# control.net
KiCad netlist of a schematic drawn in EAGLE
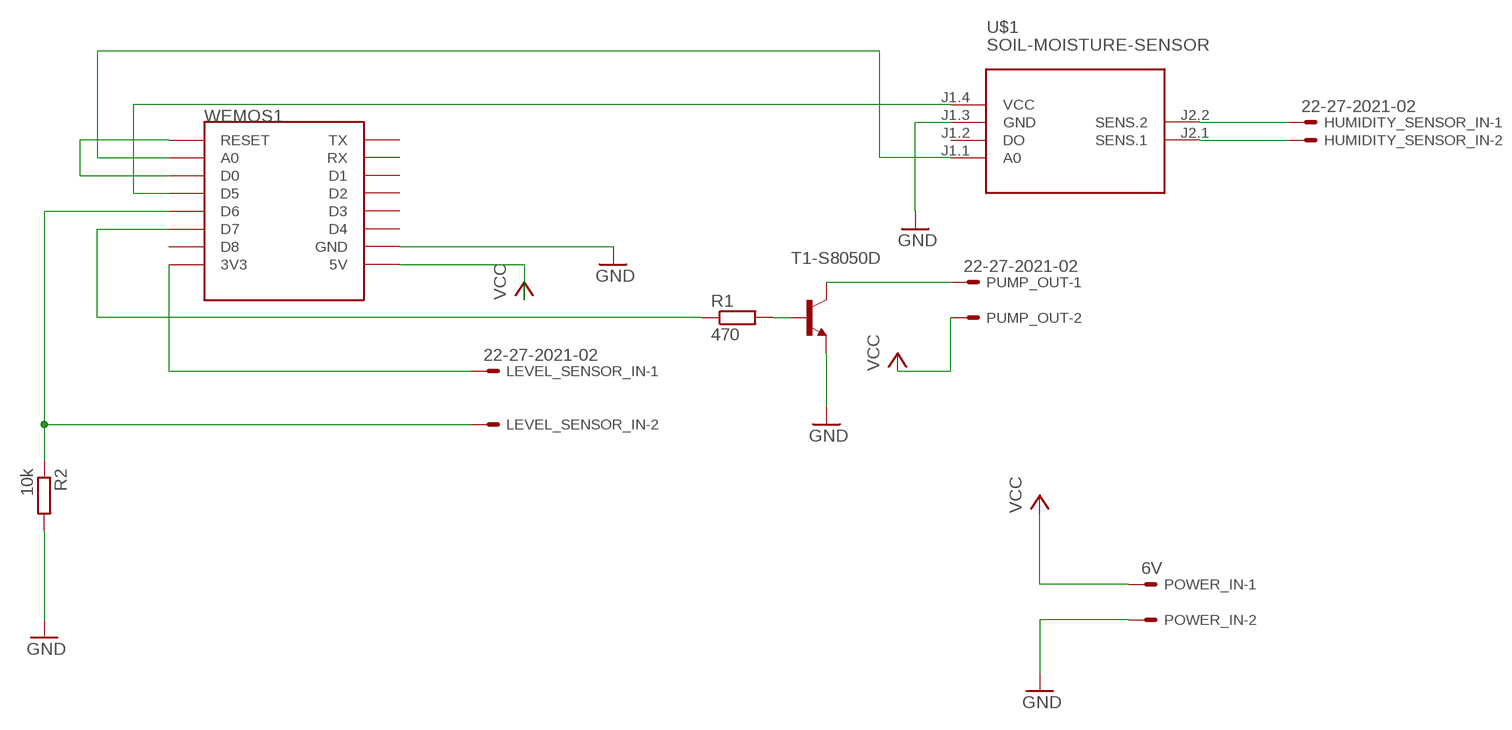
[diagram p0: schematic, sheet 1]

(export (version "E")
  (design (tool "Eeschema 10.0.6"))
  (components
    (comp (ref "HUMIDITY_SENSOR_IN")
      (value "22-27-2021-02")
      (footprint "eagle-import:6410-02")
      (fields (field (name "MF") "MOLEX"))
      (libsource (lib "eagle-import") (part "22-?-0227-2021"))
    )
    (comp (ref "LEVEL_SENSOR_IN")
      (value "22-27-2021-02")
      (footprint "eagle-import:6410-02")
      (fields (field (name "MF") "MOLEX"))
      (libsource (lib "eagle-import") (part "22-?-0227-2021"))
    )
    (comp (ref "POWER_IN")
      (value "6V")
      (footprint "eagle-import:6410-02")
      (fields (field (name "MF") "MOLEX"))
      (libsource (lib "eagle-import") (part "22-?-0227-2021"))
    )
    (comp (ref "PUMP_OUT")
      (value "22-27-2021-02")
      (footprint "eagle-import:6410-02")
      (fields (field (name "MF") "MOLEX"))
      (libsource (lib "eagle-import") (part "22-?-0227-2021"))
    )
    (comp (ref "R1")
      (value "470")
      (footprint "eagle-import:0204_7")
      (libsource (lib "eagle-import") (part "R0204/7"))
    )
    (comp (ref "R2")
      (value "10k")
      (footprint "eagle-import:0204_7")
      (libsource (lib "eagle-import") (part "R0204/7"))
    )
    (comp (ref "T1-S8050D")
      (value "-NPN-TO92")
      (footprint "eagle-import:TO92")
      (libsource (lib "eagle-import") (part "-NPN-TO92"))
    )
    (comp (ref "U$1")
      (value "SOIL-MOISTURE-SENSOR")
      (footprint "eagle-import:SOIL-MOISTURE-SENSOR")
      (libsource (lib "eagle-import") (part "SOIL-MOISTURE-SENSOR"))
    )
    (comp (ref "WEMOS1")
      (value "WEMOS-D1-MINI")
      (footprint "eagle-import:WEMOS-D1-MINI")
      (libsource (lib "eagle-import") (part "WEMOS-D1-MINI"))
    )
  )
  (nets
    (net (code "1") (name "GND") (class "Default")
      (node (ref "POWER_IN") (pin "2") (pinfunction "S_2") (pintype "passive"))
      (node (ref "R2") (pin "2") (pinfunction "2_2") (pintype "passive"))
      (node (ref "T1-S8050D") (pin "1") (pinfunction "E_1") (pintype "passive"))
      (node (ref "U$1") (pin "J1.3") (pinfunction "GND_J1.3") (pintype "power_in"))
      (node (ref "WEMOS1") (pin "GND") (pinfunction "GND_GND") (pintype "bidirectional"))
    )
    (net (code "2") (name "Net-(HUMIDITY_SENSOR_INA-S)") (class "Default")
      (node (ref "HUMIDITY_SENSOR_IN") (pin "1") (pinfunction "S_1") (pintype "passive"))
      (node (ref "U$1") (pin "J2.2") (pinfunction "SENS.2_J2.2") (pintype "bidirectional"))
    )
    (net (code "3") (name "Net-(HUMIDITY_SENSOR_INB-S)") (class "Default")
      (node (ref "HUMIDITY_SENSOR_IN") (pin "2") (pinfunction "S_2") (pintype "passive"))
      (node (ref "U$1") (pin "J2.1") (pinfunction "SENS.1_J2.1") (pintype "bidirectional"))
    )
    (net (code "4") (name "Net-(LEVEL_SENSOR_INA-S)") (class "Default")
      (node (ref "LEVEL_SENSOR_IN") (pin "1") (pinfunction "S_1") (pintype "passive"))
      (node (ref "WEMOS1") (pin "3V3") (pinfunction "3V3_3V3") (pintype "bidirectional"))
    )
    (net (code "5") (name "Net-(LEVEL_SENSOR_INB-S)") (class "Default")
      (node (ref "LEVEL_SENSOR_IN") (pin "2") (pinfunction "S_2") (pintype "passive"))
      (node (ref "R2") (pin "1") (pinfunction "1_1") (pintype "passive"))
      (node (ref "WEMOS1") (pin "D6") (pinfunction "D6_D6") (pintype "bidirectional"))
    )
    (net (code "6") (name "Net-(PUMP_OUTA-S)") (class "Default")
      (node (ref "PUMP_OUT") (pin "1") (pinfunction "S_1") (pintype "passive"))
      (node (ref "T1-S8050D") (pin "3") (pinfunction "C_3") (pintype "passive"))
    )
    (net (code "7") (name "Net-(R1-Pad1)") (class "Default")
      (node (ref "R1") (pin "1") (pinfunction "1_1") (pintype "passive"))
      (node (ref "WEMOS1") (pin "D7") (pinfunction "D7_D7") (pintype "bidirectional"))
    )
    (net (code "8") (name "Net-(T1-S8050D-B)") (class "Default")
      (node (ref "R1") (pin "2") (pinfunction "2_2") (pintype "passive"))
      (node (ref "T1-S8050D") (pin "2") (pinfunction "B_2") (pintype "passive"))
    )
    (net (code "9") (name "Net-(U$1-A0)") (class "Default")
      (node (ref "U$1") (pin "J1.1") (pinfunction "A0_J1.1") (pintype "bidirectional"))
      (node (ref "WEMOS1") (pin "A0") (pinfunction "A0_A0") (pintype "bidirectional"))
    )
    (net (code "10") (name "Net-(U$1-VCC)") (class "Default")
      (node (ref "U$1") (pin "J1.4") (pinfunction "VCC_J1.4") (pintype "power_in"))
      (node (ref "WEMOS1") (pin "D5") (pinfunction "D5_D5") (pintype "bidirectional"))
    )
    (net (code "11") (name "Net-(WEMOS1-PadD0)") (class "Default")
      (node (ref "WEMOS1") (pin "D0") (pinfunction "D0_D0") (pintype "bidirectional"))
      (node (ref "WEMOS1") (pin "RESET") (pinfunction "RESET_RESET") (pintype "bidirectional"))
    )
    (net (code "12") (name "VCC") (class "Default")
      (node (ref "POWER_IN") (pin "1") (pinfunction "S_1") (pintype "passive"))
      (node (ref "PUMP_OUT") (pin "2") (pinfunction "S_2") (pintype "passive"))
      (node (ref "WEMOS1") (pin "5V") (pinfunction "5V_5V") (pintype "bidirectional"))
    )
    (net (code "13") (name "unconnected-(U$1-DO-PadJ1.2)") (class "Default")
      (node (ref "U$1") (pin "J1.2") (pinfunction "DO_J1.2") (pintype "output"))
    )
    (net (code "14") (name "unconnected-(WEMOS1-PadD1)") (class "Default")
      (node (ref "WEMOS1") (pin "D1") (pinfunction "D1_D1") (pintype "bidirectional"))
    )
    (net (code "15") (name "unconnected-(WEMOS1-PadD2)") (class "Default")
      (node (ref "WEMOS1") (pin "D2") (pinfunction "D2_D2") (pintype "bidirectional"))
    )
    (net (code "16") (name "unconnected-(WEMOS1-PadD3)") (class "Default")
      (node (ref "WEMOS1") (pin "D3") (pinfunction "D3_D3") (pintype "bidirectional"))
    )
    (net (code "17") (name "unconnected-(WEMOS1-PadD4)") (class "Default")
      (node (ref "WEMOS1") (pin "D4") (pinfunction "D4_D4") (pintype "bidirectional"))
    )
    (net (code "18") (name "unconnected-(WEMOS1-PadD8)") (class "Default")
      (node (ref "WEMOS1") (pin "D8") (pinfunction "D8_D8") (pintype "bidirectional"))
    )
    (net (code "19") (name "unconnected-(WEMOS1-PadRX)") (class "Default")
      (node (ref "WEMOS1") (pin "RX") (pinfunction "RX_RX") (pintype "bidirectional"))
    )
    (net (code "20") (name "unconnected-(WEMOS1-PadTX)") (class "Default")
      (node (ref "WEMOS1") (pin "TX") (pinfunction "TX_TX") (pintype "bidirectional"))
    )
  )
)
